# nrf24l01_mboard.net
KiCad netlist of a schematic drawn in Altium Designer
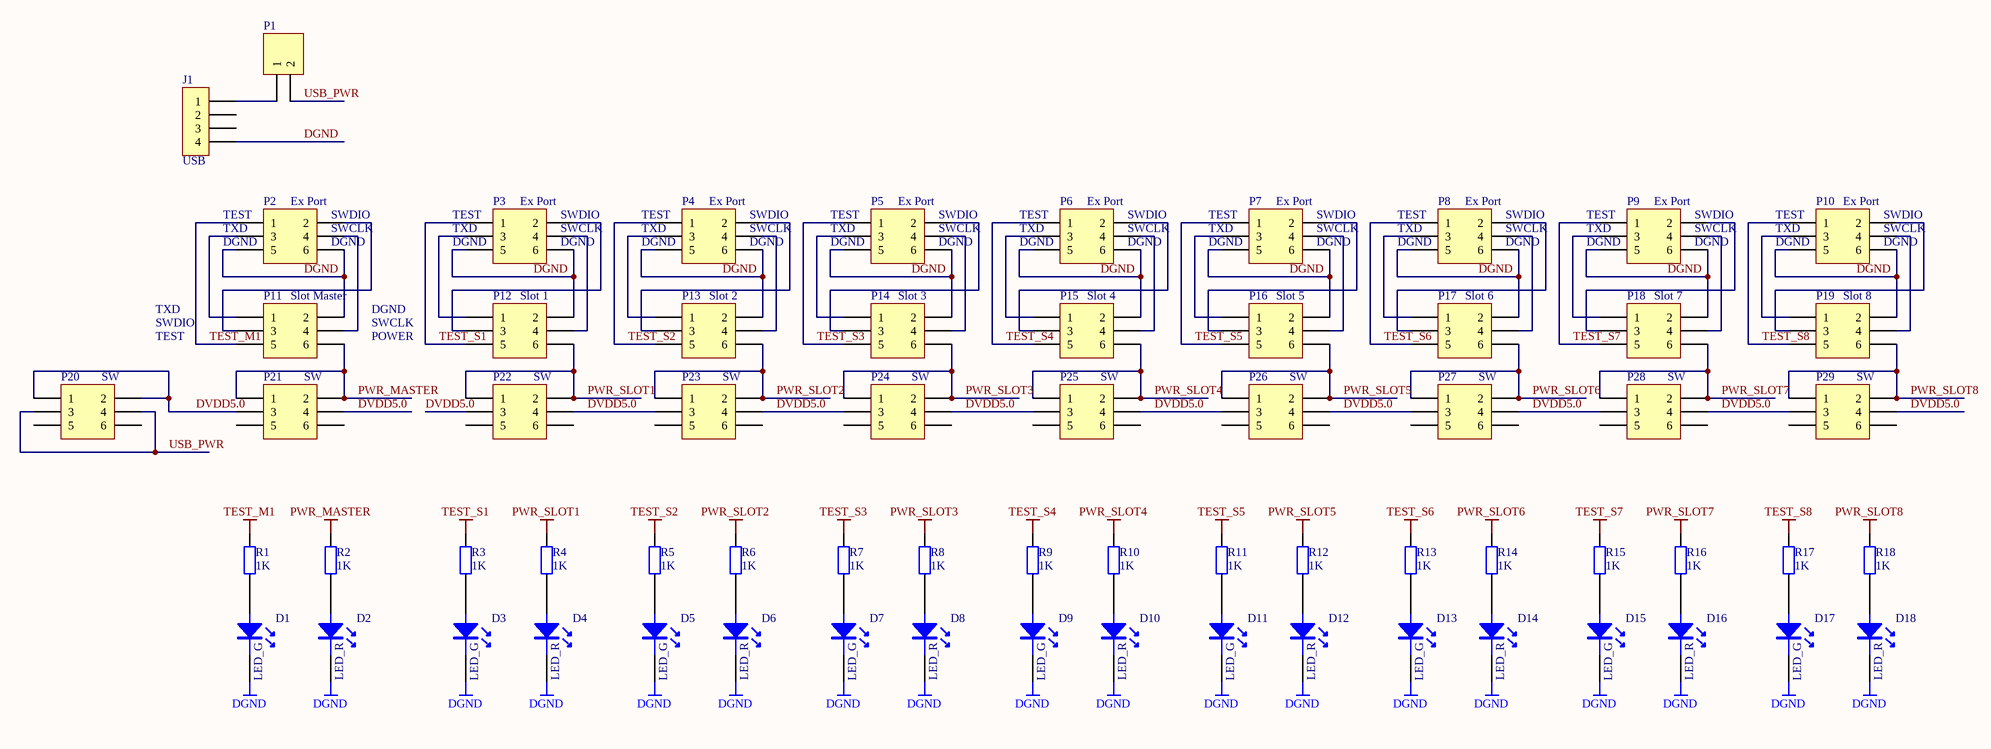
[diagram p0: nrf24l01_mboard.SchDoc]

(export (version "E")
  (design (tool "Eeschema 10.0.6"))
  (components
    (comp (ref "D1") (value "LED_G") (footprint "LED-0603R") (libsource (lib "*") (part "LED")))
    (comp (ref "D2") (value "LED_R") (footprint "LED-0603R") (libsource (lib "*") (part "LED")))
    (comp (ref "D3") (value "LED_G") (footprint "LED-0603R") (libsource (lib "*") (part "LED")))
    (comp (ref "D4") (value "LED_R") (footprint "LED-0603R") (libsource (lib "*") (part "LED")))
    (comp (ref "D5") (value "LED_G") (footprint "LED-0603R") (libsource (lib "*") (part "LED")))
    (comp (ref "D6") (value "LED_R") (footprint "LED-0603R") (libsource (lib "*") (part "LED")))
    (comp (ref "D7") (value "LED_G") (footprint "LED-0603R") (libsource (lib "*") (part "LED")))
    (comp (ref "D8") (value "LED_R") (footprint "LED-0603R") (libsource (lib "*") (part "LED")))
    (comp (ref "D9") (value "LED_G") (footprint "LED-0603R") (libsource (lib "*") (part "LED")))
    (comp (ref "D10") (value "LED_R") (footprint "LED-0603R") (libsource (lib "*") (part "LED")))
    (comp (ref "D11") (value "LED_G") (footprint "LED-0603R") (libsource (lib "*") (part "LED")))
    (comp (ref "D12") (value "LED_R") (footprint "LED-0603R") (libsource (lib "*") (part "LED")))
    (comp (ref "D13") (value "LED_G") (footprint "LED-0603R") (libsource (lib "*") (part "LED")))
    (comp (ref "D14") (value "LED_R") (footprint "LED-0603R") (libsource (lib "*") (part "LED")))
    (comp (ref "D15") (value "LED_G") (footprint "LED-0603R") (libsource (lib "*") (part "LED")))
    (comp (ref "D16") (value "LED_R") (footprint "LED-0603R") (libsource (lib "*") (part "LED")))
    (comp (ref "D17") (value "LED_G") (footprint "LED-0603R") (libsource (lib "*") (part "LED")))
    (comp (ref "D18") (value "LED_R") (footprint "LED-0603R") (libsource (lib "*") (part "LED")))
    (comp (ref "J1")
      (value "USB")
      (footprint "USB-MINIB")
      (description "Connector")
      (libsource (lib "*") (part "CON4"))
    )
    (comp (ref "P1")
      (value "~")
      (footprint "HDR1X2")
      (description "Header, 2-Pin")
      (fields (field (name "PUBLISHER") "Altium Limited"))
      (libsource (lib "Miscellaneous Connectors") (part "Header 2"))
    )
    (comp (ref "P2")
      (value "Ex Port")
      (footprint "IDC6")
      (description "Header, 3-Pin, Dual row")
      (fields (field (name "PUBLISHER") "Altium Limited"))
      (libsource (lib "Miscellaneous Connectors") (part "Header 3X2"))
    )
    (comp (ref "P3")
      (value "Ex Port")
      (footprint "IDC6")
      (description "Header, 3-Pin, Dual row")
      (fields (field (name "PUBLISHER") "Altium Limited"))
      (libsource (lib "Miscellaneous Connectors") (part "Header 3X2"))
    )
    (comp (ref "P4")
      (value "Ex Port")
      (footprint "IDC6")
      (description "Header, 3-Pin, Dual row")
      (fields (field (name "PUBLISHER") "Altium Limited"))
      (libsource (lib "Miscellaneous Connectors") (part "Header 3X2"))
    )
    (comp (ref "P5")
      (value "Ex Port")
      (footprint "IDC6")
      (description "Header, 3-Pin, Dual row")
      (fields (field (name "PUBLISHER") "Altium Limited"))
      (libsource (lib "Miscellaneous Connectors") (part "Header 3X2"))
    )
    (comp (ref "P6")
      (value "Ex Port")
      (footprint "IDC6")
      (description "Header, 3-Pin, Dual row")
      (fields (field (name "PUBLISHER") "Altium Limited"))
      (libsource (lib "Miscellaneous Connectors") (part "Header 3X2"))
    )
    (comp (ref "P7")
      (value "Ex Port")
      (footprint "IDC6")
      (description "Header, 3-Pin, Dual row")
      (fields (field (name "PUBLISHER") "Altium Limited"))
      (libsource (lib "Miscellaneous Connectors") (part "Header 3X2"))
    )
    (comp (ref "P8")
      (value "Ex Port")
      (footprint "IDC6")
      (description "Header, 3-Pin, Dual row")
      (fields (field (name "PUBLISHER") "Altium Limited"))
      (libsource (lib "Miscellaneous Connectors") (part "Header 3X2"))
    )
    (comp (ref "P9")
      (value "Ex Port")
      (footprint "IDC6")
      (description "Header, 3-Pin, Dual row")
      (fields (field (name "PUBLISHER") "Altium Limited"))
      (libsource (lib "Miscellaneous Connectors") (part "Header 3X2"))
    )
    (comp (ref "P10")
      (value "Ex Port")
      (footprint "IDC6")
      (description "Header, 3-Pin, Dual row")
      (fields (field (name "PUBLISHER") "Altium Limited"))
      (libsource (lib "Miscellaneous Connectors") (part "Header 3X2"))
    )
    (comp (ref "P11")
      (value "Slot Master")
      (footprint "S-8M-2.54-5 6P")
      (description "Header, 3-Pin, Dual row")
      (fields (field (name "PUBLISHER") "Altium Limited"))
      (libsource (lib "Miscellaneous Connectors") (part "Header 3X2"))
    )
    (comp (ref "P12")
      (value "Slot 1")
      (footprint "S-8M-2.54-5 6P")
      (description "Header, 3-Pin, Dual row")
      (fields (field (name "PUBLISHER") "Altium Limited"))
      (libsource (lib "Miscellaneous Connectors") (part "Header 3X2"))
    )
    (comp (ref "P13")
      (value "Slot 2")
      (footprint "S-8M-2.54-5 6P")
      (description "Header, 3-Pin, Dual row")
      (fields (field (name "PUBLISHER") "Altium Limited"))
      (libsource (lib "Miscellaneous Connectors") (part "Header 3X2"))
    )
    (comp (ref "P14")
      (value "Slot 3")
      (footprint "S-8M-2.54-5 6P")
      (description "Header, 3-Pin, Dual row")
      (fields (field (name "PUBLISHER") "Altium Limited"))
      (libsource (lib "Miscellaneous Connectors") (part "Header 3X2"))
    )
    (comp (ref "P15")
      (value "Slot 4")
      (footprint "S-8M-2.54-5 6P")
      (description "Header, 3-Pin, Dual row")
      (fields (field (name "PUBLISHER") "Altium Limited"))
      (libsource (lib "Miscellaneous Connectors") (part "Header 3X2"))
    )
    (comp (ref "P16")
      (value "Slot 5")
      (footprint "S-8M-2.54-5 6P")
      (description "Header, 3-Pin, Dual row")
      (fields (field (name "PUBLISHER") "Altium Limited"))
      (libsource (lib "Miscellaneous Connectors") (part "Header 3X2"))
    )
    (comp (ref "P17")
      (value "Slot 6")
      (footprint "S-8M-2.54-5 6P")
      (description "Header, 3-Pin, Dual row")
      (fields (field (name "PUBLISHER") "Altium Limited"))
      (libsource (lib "Miscellaneous Connectors") (part "Header 3X2"))
    )
    (comp (ref "P18")
      (value "Slot 7")
      (footprint "S-8M-2.54-5 6P")
      (description "Header, 3-Pin, Dual row")
      (fields (field (name "PUBLISHER") "Altium Limited"))
      (libsource (lib "Miscellaneous Connectors") (part "Header 3X2"))
    )
    (comp (ref "P19")
      (value "Slot 8")
      (footprint "S-8M-2.54-5 6P")
      (description "Header, 3-Pin, Dual row")
      (fields (field (name "PUBLISHER") "Altium Limited"))
      (libsource (lib "Miscellaneous Connectors") (part "Header 3X2"))
    )
    (comp (ref "P20")
      (value "SW")
      (footprint "SW-7x7")
      (description "Header, 3-Pin, Dual row")
      (fields (field (name "PUBLISHER") "Altium Limited"))
      (libsource (lib "Miscellaneous Connectors") (part "Header 3X2"))
    )
    (comp (ref "P21")
      (value "SW")
      (footprint "SW-7x7")
      (description "Header, 3-Pin, Dual row")
      (fields (field (name "PUBLISHER") "Altium Limited"))
      (libsource (lib "Miscellaneous Connectors") (part "Header 3X2"))
    )
    (comp (ref "P22")
      (value "SW")
      (footprint "SW-7x7")
      (description "Header, 3-Pin, Dual row")
      (fields (field (name "PUBLISHER") "Altium Limited"))
      (libsource (lib "Miscellaneous Connectors") (part "Header 3X2"))
    )
    (comp (ref "P23")
      (value "SW")
      (footprint "SW-7x7")
      (description "Header, 3-Pin, Dual row")
      (fields (field (name "PUBLISHER") "Altium Limited"))
      (libsource (lib "Miscellaneous Connectors") (part "Header 3X2"))
    )
    (comp (ref "P24")
      (value "SW")
      (footprint "SW-7x7")
      (description "Header, 3-Pin, Dual row")
      (fields (field (name "PUBLISHER") "Altium Limited"))
      (libsource (lib "Miscellaneous Connectors") (part "Header 3X2"))
    )
    (comp (ref "P25")
      (value "SW")
      (footprint "SW-7x7")
      (description "Header, 3-Pin, Dual row")
      (fields (field (name "PUBLISHER") "Altium Limited"))
      (libsource (lib "Miscellaneous Connectors") (part "Header 3X2"))
    )
    (comp (ref "P26")
      (value "SW")
      (footprint "SW-7x7")
      (description "Header, 3-Pin, Dual row")
      (fields (field (name "PUBLISHER") "Altium Limited"))
      (libsource (lib "Miscellaneous Connectors") (part "Header 3X2"))
    )
    (comp (ref "P27")
      (value "SW")
      (footprint "SW-7x7")
      (description "Header, 3-Pin, Dual row")
      (fields (field (name "PUBLISHER") "Altium Limited"))
      (libsource (lib "Miscellaneous Connectors") (part "Header 3X2"))
    )
    (comp (ref "P28")
      (value "SW")
      (footprint "SW-7x7")
      (description "Header, 3-Pin, Dual row")
      (fields (field (name "PUBLISHER") "Altium Limited"))
      (libsource (lib "Miscellaneous Connectors") (part "Header 3X2"))
    )
    (comp (ref "P29")
      (value "SW")
      (footprint "SW-7x7")
      (description "Header, 3-Pin, Dual row")
      (fields (field (name "PUBLISHER") "Altium Limited"))
      (libsource (lib "Miscellaneous Connectors") (part "Header 3X2"))
    )
    (comp (ref "R1")
      (value "1K")
      (footprint "1608(0603R)")
      (description "Resistor")
      (fields (field (name "PUBLISHER") "Altium Limited"))
      (libsource (lib "Miscellaneous Devices") (part "Res2"))
    )
    (comp (ref "R2")
      (value "1K")
      (footprint "1608(0603R)")
      (description "Resistor")
      (fields (field (name "PUBLISHER") "Altium Limited"))
      (libsource (lib "Miscellaneous Devices") (part "Res2"))
    )
    (comp (ref "R3")
      (value "1K")
      (footprint "1608(0603R)")
      (description "Resistor")
      (fields (field (name "PUBLISHER") "Altium Limited"))
      (libsource (lib "Miscellaneous Devices") (part "Res2"))
    )
    (comp (ref "R4")
      (value "1K")
      (footprint "1608(0603R)")
      (description "Resistor")
      (fields (field (name "PUBLISHER") "Altium Limited"))
      (libsource (lib "Miscellaneous Devices") (part "Res2"))
    )
    (comp (ref "R5")
      (value "1K")
      (footprint "1608(0603R)")
      (description "Resistor")
      (fields (field (name "PUBLISHER") "Altium Limited"))
      (libsource (lib "Miscellaneous Devices") (part "Res2"))
    )
    (comp (ref "R6")
      (value "1K")
      (footprint "1608(0603R)")
      (description "Resistor")
      (fields (field (name "PUBLISHER") "Altium Limited"))
      (libsource (lib "Miscellaneous Devices") (part "Res2"))
    )
    (comp (ref "R7")
      (value "1K")
      (footprint "1608(0603R)")
      (description "Resistor")
      (fields (field (name "PUBLISHER") "Altium Limited"))
      (libsource (lib "Miscellaneous Devices") (part "Res2"))
    )
    (comp (ref "R8")
      (value "1K")
      (footprint "1608(0603R)")
      (description "Resistor")
      (fields (field (name "PUBLISHER") "Altium Limited"))
      (libsource (lib "Miscellaneous Devices") (part "Res2"))
    )
    (comp (ref "R9")
      (value "1K")
      (footprint "1608(0603R)")
      (description "Resistor")
      (fields (field (name "PUBLISHER") "Altium Limited"))
      (libsource (lib "Miscellaneous Devices") (part "Res2"))
    )
    (comp (ref "R10")
      (value "1K")
      (footprint "1608(0603R)")
      (description "Resistor")
      (fields (field (name "PUBLISHER") "Altium Limited"))
      (libsource (lib "Miscellaneous Devices") (part "Res2"))
    )
    (comp (ref "R11")
      (value "1K")
      (footprint "1608(0603R)")
      (description "Resistor")
      (fields (field (name "PUBLISHER") "Altium Limited"))
      (libsource (lib "Miscellaneous Devices") (part "Res2"))
    )
    (comp (ref "R12")
      (value "1K")
      (footprint "1608(0603R)")
      (description "Resistor")
      (fields (field (name "PUBLISHER") "Altium Limited"))
      (libsource (lib "Miscellaneous Devices") (part "Res2"))
    )
    (comp (ref "R13")
      (value "1K")
      (footprint "1608(0603R)")
      (description "Resistor")
      (fields (field (name "PUBLISHER") "Altium Limited"))
      (libsource (lib "Miscellaneous Devices") (part "Res2"))
    )
    (comp (ref "R14")
      (value "1K")
      (footprint "1608(0603R)")
      (description "Resistor")
      (fields (field (name "PUBLISHER") "Altium Limited"))
      (libsource (lib "Miscellaneous Devices") (part "Res2"))
    )
    (comp (ref "R15")
      (value "1K")
      (footprint "1608(0603R)")
      (description "Resistor")
      (fields (field (name "PUBLISHER") "Altium Limited"))
      (libsource (lib "Miscellaneous Devices") (part "Res2"))
    )
    (comp (ref "R16")
      (value "1K")
      (footprint "1608(0603R)")
      (description "Resistor")
      (fields (field (name "PUBLISHER") "Altium Limited"))
      (libsource (lib "Miscellaneous Devices") (part "Res2"))
    )
    (comp (ref "R17")
      (value "1K")
      (footprint "1608(0603R)")
      (description "Resistor")
      (fields (field (name "PUBLISHER") "Altium Limited"))
      (libsource (lib "Miscellaneous Devices") (part "Res2"))
    )
    (comp (ref "R18")
      (value "1K")
      (footprint "1608(0603R)")
      (description "Resistor")
      (fields (field (name "PUBLISHER") "Altium Limited"))
      (libsource (lib "Miscellaneous Devices") (part "Res2"))
    )
  )
  (nets
    (net (code "1") (name "/DVDD5.0") (class "Default")
      (node (ref "P20") (pin "1") (pinfunction "1_1") (pintype "passive"))
      (node (ref "P20") (pin "2") (pinfunction "2_2") (pintype "passive"))
      (node (ref "P21") (pin "3") (pinfunction "3_3") (pintype "passive"))
      (node (ref "P21") (pin "4") (pinfunction "4_4") (pintype "passive"))
      (node (ref "P22") (pin "3") (pinfunction "3_3") (pintype "passive"))
      (node (ref "P22") (pin "4") (pinfunction "4_4") (pintype "passive"))
      (node (ref "P23") (pin "3") (pinfunction "3_3") (pintype "passive"))
      (node (ref "P23") (pin "4") (pinfunction "4_4") (pintype "passive"))
      (node (ref "P24") (pin "3") (pinfunction "3_3") (pintype "passive"))
      (node (ref "P24") (pin "4") (pinfunction "4_4") (pintype "passive"))
      (node (ref "P25") (pin "3") (pinfunction "3_3") (pintype "passive"))
      (node (ref "P25") (pin "4") (pinfunction "4_4") (pintype "passive"))
      (node (ref "P26") (pin "3") (pinfunction "3_3") (pintype "passive"))
      (node (ref "P26") (pin "4") (pinfunction "4_4") (pintype "passive"))
      (node (ref "P27") (pin "3") (pinfunction "3_3") (pintype "passive"))
      (node (ref "P27") (pin "4") (pinfunction "4_4") (pintype "passive"))
      (node (ref "P28") (pin "3") (pinfunction "3_3") (pintype "passive"))
      (node (ref "P28") (pin "4") (pinfunction "4_4") (pintype "passive"))
      (node (ref "P29") (pin "3") (pinfunction "3_3") (pintype "passive"))
      (node (ref "P29") (pin "4") (pinfunction "4_4") (pintype "passive"))
    )
    (net (code "2") (name "/USB_PWR") (class "Default")
      (node (ref "P1") (pin "2") (pinfunction "2_2") (pintype "passive"))
      (node (ref "P20") (pin "3") (pinfunction "3_3") (pintype "passive"))
      (node (ref "P20") (pin "4") (pinfunction "4_4") (pintype "passive"))
    )
    (net (code "3") (name "DGND") (class "Default")
      (node (ref "D1") (pin "K") (pinfunction "2_K") (pintype "passive"))
      (node (ref "D10") (pin "K") (pinfunction "2_K") (pintype "passive"))
      (node (ref "D11") (pin "K") (pinfunction "2_K") (pintype "passive"))
      (node (ref "D12") (pin "K") (pinfunction "2_K") (pintype "passive"))
      (node (ref "D13") (pin "K") (pinfunction "2_K") (pintype "passive"))
      (node (ref "D14") (pin "K") (pinfunction "2_K") (pintype "passive"))
      (node (ref "D15") (pin "K") (pinfunction "2_K") (pintype "passive"))
      (node (ref "D16") (pin "K") (pinfunction "2_K") (pintype "passive"))
      (node (ref "D17") (pin "K") (pinfunction "2_K") (pintype "passive"))
      (node (ref "D18") (pin "K") (pinfunction "2_K") (pintype "passive"))
      (node (ref "D2") (pin "K") (pinfunction "2_K") (pintype "passive"))
      (node (ref "D3") (pin "K") (pinfunction "2_K") (pintype "passive"))
      (node (ref "D4") (pin "K") (pinfunction "2_K") (pintype "passive"))
      (node (ref "D5") (pin "K") (pinfunction "2_K") (pintype "passive"))
      (node (ref "D6") (pin "K") (pinfunction "2_K") (pintype "passive"))
      (node (ref "D7") (pin "K") (pinfunction "2_K") (pintype "passive"))
      (node (ref "D8") (pin "K") (pinfunction "2_K") (pintype "passive"))
      (node (ref "D9") (pin "K") (pinfunction "2_K") (pintype "passive"))
      (node (ref "J1") (pin "4") (pinfunction "4_4") (pintype "passive"))
      (node (ref "P10") (pin "5") (pinfunction "5_5") (pintype "passive"))
      (node (ref "P10") (pin "6") (pinfunction "6_6") (pintype "passive"))
      (node (ref "P11") (pin "2") (pinfunction "2_2") (pintype "passive"))
      (node (ref "P12") (pin "2") (pinfunction "2_2") (pintype "passive"))
      (node (ref "P13") (pin "2") (pinfunction "2_2") (pintype "passive"))
      (node (ref "P14") (pin "2") (pinfunction "2_2") (pintype "passive"))
      (node (ref "P15") (pin "2") (pinfunction "2_2") (pintype "passive"))
      (node (ref "P16") (pin "2") (pinfunction "2_2") (pintype "passive"))
      (node (ref "P17") (pin "2") (pinfunction "2_2") (pintype "passive"))
      (node (ref "P18") (pin "2") (pinfunction "2_2") (pintype "passive"))
      (node (ref "P19") (pin "2") (pinfunction "2_2") (pintype "passive"))
      (node (ref "P2") (pin "5") (pinfunction "5_5") (pintype "passive"))
      (node (ref "P2") (pin "6") (pinfunction "6_6") (pintype "passive"))
      (node (ref "P3") (pin "5") (pinfunction "5_5") (pintype "passive"))
      (node (ref "P3") (pin "6") (pinfunction "6_6") (pintype "passive"))
      (node (ref "P4") (pin "5") (pinfunction "5_5") (pintype "passive"))
      (node (ref "P4") (pin "6") (pinfunction "6_6") (pintype "passive"))
      (node (ref "P5") (pin "5") (pinfunction "5_5") (pintype "passive"))
      (node (ref "P5") (pin "6") (pinfunction "6_6") (pintype "passive"))
      (node (ref "P6") (pin "5") (pinfunction "5_5") (pintype "passive"))
      (node (ref "P6") (pin "6") (pinfunction "6_6") (pintype "passive"))
      (node (ref "P7") (pin "5") (pinfunction "5_5") (pintype "passive"))
      (node (ref "P7") (pin "6") (pinfunction "6_6") (pintype "passive"))
      (node (ref "P8") (pin "5") (pinfunction "5_5") (pintype "passive"))
      (node (ref "P8") (pin "6") (pinfunction "6_6") (pintype "passive"))
      (node (ref "P9") (pin "5") (pinfunction "5_5") (pintype "passive"))
      (node (ref "P9") (pin "6") (pinfunction "6_6") (pintype "passive"))
    )
    (net (code "4") (name "Net-(D1-1)") (class "Default")
      (node (ref "D1") (pin "A") (pinfunction "1_A") (pintype "passive"))
      (node (ref "R1") (pin "2") (pinfunction "2_2") (pintype "passive"))
    )
    (net (code "5") (name "Net-(D2-1)") (class "Default")
      (node (ref "D2") (pin "A") (pinfunction "1_A") (pintype "passive"))
      (node (ref "R2") (pin "2") (pinfunction "2_2") (pintype "passive"))
    )
    (net (code "6") (name "Net-(D3-1)") (class "Default")
      (node (ref "D3") (pin "A") (pinfunction "1_A") (pintype "passive"))
      (node (ref "R3") (pin "2") (pinfunction "2_2") (pintype "passive"))
    )
    (net (code "7") (name "Net-(D4-1)") (class "Default")
      (node (ref "D4") (pin "A") (pinfunction "1_A") (pintype "passive"))
      (node (ref "R4") (pin "2") (pinfunction "2_2") (pintype "passive"))
    )
    (net (code "8") (name "Net-(D5-1)") (class "Default")
      (node (ref "D5") (pin "A") (pinfunction "1_A") (pintype "passive"))
      (node (ref "R5") (pin "2") (pinfunction "2_2") (pintype "passive"))
    )
    (net (code "9") (name "Net-(D6-1)") (class "Default")
      (node (ref "D6") (pin "A") (pinfunction "1_A") (pintype "passive"))
      (node (ref "R6") (pin "2") (pinfunction "2_2") (pintype "passive"))
    )
    (net (code "10") (name "Net-(D7-1)") (class "Default")
      (node (ref "D7") (pin "A") (pinfunction "1_A") (pintype "passive"))
      (node (ref "R7") (pin "2") (pinfunction "2_2") (pintype "passive"))
    )
    (net (code "11") (name "Net-(D8-1)") (class "Default")
      (node (ref "D8") (pin "A") (pinfunction "1_A") (pintype "passive"))
      (node (ref "R8") (pin "2") (pinfunction "2_2") (pintype "passive"))
    )
    (net (code "12") (name "Net-(D9-1)") (class "Default")
      (node (ref "D9") (pin "A") (pinfunction "1_A") (pintype "passive"))
      (node (ref "R9") (pin "2") (pinfunction "2_2") (pintype "passive"))
    )
    (net (code "13") (name "Net-(D10-1)") (class "Default")
      (node (ref "D10") (pin "A") (pinfunction "1_A") (pintype "passive"))
      (node (ref "R10") (pin "2") (pinfunction "2_2") (pintype "passive"))
    )
    (net (code "14") (name "Net-(D11-1)") (class "Default")
      (node (ref "D11") (pin "A") (pinfunction "1_A") (pintype "passive"))
      (node (ref "R11") (pin "2") (pinfunction "2_2") (pintype "passive"))
    )
    (net (code "15") (name "Net-(D12-1)") (class "Default")
      (node (ref "D12") (pin "A") (pinfunction "1_A") (pintype "passive"))
      (node (ref "R12") (pin "2") (pinfunction "2_2") (pintype "passive"))
    )
    (net (code "16") (name "Net-(D13-1)") (class "Default")
      (node (ref "D13") (pin "A") (pinfunction "1_A") (pintype "passive"))
      (node (ref "R13") (pin "2") (pinfunction "2_2") (pintype "passive"))
    )
    (net (code "17") (name "Net-(D14-1)") (class "Default")
      (node (ref "D14") (pin "A") (pinfunction "1_A") (pintype "passive"))
      (node (ref "R14") (pin "2") (pinfunction "2_2") (pintype "passive"))
    )
    (net (code "18") (name "Net-(D15-1)") (class "Default")
      (node (ref "D15") (pin "A") (pinfunction "1_A") (pintype "passive"))
      (node (ref "R15") (pin "2") (pinfunction "2_2") (pintype "passive"))
    )
    (net (code "19") (name "Net-(D16-1)") (class "Default")
      (node (ref "D16") (pin "A") (pinfunction "1_A") (pintype "passive"))
      (node (ref "R16") (pin "2") (pinfunction "2_2") (pintype "passive"))
    )
    (net (code "20") (name "Net-(D17-1)") (class "Default")
      (node (ref "D17") (pin "A") (pinfunction "1_A") (pintype "passive"))
      (node (ref "R17") (pin "2") (pinfunction "2_2") (pintype "passive"))
    )
    (net (code "21") (name "Net-(D18-1)") (class "Default")
      (node (ref "D18") (pin "A") (pinfunction "1_A") (pintype "passive"))
      (node (ref "R18") (pin "2") (pinfunction "2_2") (pintype "passive"))
    )
    (net (code "22") (name "Net-(J1-Pad1)") (class "Default")
      (node (ref "J1") (pin "1") (pinfunction "1_1") (pintype "passive"))
      (node (ref "P1") (pin "1") (pinfunction "1_1") (pintype "passive"))
    )
    (net (code "23") (name "Net-(P10-Pad2)") (class "Default")
      (node (ref "P10") (pin "2") (pinfunction "2_2") (pintype "passive"))
      (node (ref "P19") (pin "3") (pinfunction "3_3") (pintype "passive"))
    )
    (net (code "24") (name "Net-(P10-Pad3)") (class "Default")
      (node (ref "P10") (pin "3") (pinfunction "3_3") (pintype "passive"))
      (node (ref "P19") (pin "1") (pinfunction "1_1") (pintype "passive"))
    )
    (net (code "25") (name "Net-(P10-Pad4)") (class "Default")
      (node (ref "P10") (pin "4") (pinfunction "4_4") (pintype "passive"))
      (node (ref "P19") (pin "4") (pinfunction "4_4") (pintype "passive"))
    )
    (net (code "26") (name "Net-(P11-Pad1)") (class "Default")
      (node (ref "P11") (pin "1") (pinfunction "1_1") (pintype "passive"))
      (node (ref "P2") (pin "3") (pinfunction "3_3") (pintype "passive"))
    )
    (net (code "27") (name "Net-(P11-Pad3)") (class "Default")
      (node (ref "P11") (pin "3") (pinfunction "3_3") (pintype "passive"))
      (node (ref "P2") (pin "2") (pinfunction "2_2") (pintype "passive"))
    )
    (net (code "28") (name "Net-(P11-Pad4)") (class "Default")
      (node (ref "P11") (pin "4") (pinfunction "4_4") (pintype "passive"))
      (node (ref "P2") (pin "4") (pinfunction "4_4") (pintype "passive"))
    )
    (net (code "29") (name "Net-(P12-Pad1)") (class "Default")
      (node (ref "P12") (pin "1") (pinfunction "1_1") (pintype "passive"))
      (node (ref "P3") (pin "3") (pinfunction "3_3") (pintype "passive"))
    )
    (net (code "30") (name "Net-(P12-Pad3)") (class "Default")
      (node (ref "P12") (pin "3") (pinfunction "3_3") (pintype "passive"))
      (node (ref "P3") (pin "2") (pinfunction "2_2") (pintype "passive"))
    )
    (net (code "31") (name "Net-(P12-Pad4)") (class "Default")
      (node (ref "P12") (pin "4") (pinfunction "4_4") (pintype "passive"))
      (node (ref "P3") (pin "4") (pinfunction "4_4") (pintype "passive"))
    )
    (net (code "32") (name "Net-(P13-Pad1)") (class "Default")
      (node (ref "P13") (pin "1") (pinfunction "1_1") (pintype "passive"))
      (node (ref "P4") (pin "3") (pinfunction "3_3") (pintype "passive"))
    )
    (net (code "33") (name "Net-(P13-Pad3)") (class "Default")
      (node (ref "P13") (pin "3") (pinfunction "3_3") (pintype "passive"))
      (node (ref "P4") (pin "2") (pinfunction "2_2") (pintype "passive"))
    )
    (net (code "34") (name "Net-(P13-Pad4)") (class "Default")
      (node (ref "P13") (pin "4") (pinfunction "4_4") (pintype "passive"))
      (node (ref "P4") (pin "4") (pinfunction "4_4") (pintype "passive"))
    )
    (net (code "35") (name "Net-(P14-Pad1)") (class "Default")
      (node (ref "P14") (pin "1") (pinfunction "1_1") (pintype "passive"))
      (node (ref "P5") (pin "3") (pinfunction "3_3") (pintype "passive"))
    )
    (net (code "36") (name "Net-(P14-Pad3)") (class "Default")
      (node (ref "P14") (pin "3") (pinfunction "3_3") (pintype "passive"))
      (node (ref "P5") (pin "2") (pinfunction "2_2") (pintype "passive"))
    )
    (net (code "37") (name "Net-(P14-Pad4)") (class "Default")
      (node (ref "P14") (pin "4") (pinfunction "4_4") (pintype "passive"))
      (node (ref "P5") (pin "4") (pinfunction "4_4") (pintype "passive"))
    )
    (net (code "38") (name "Net-(P15-Pad1)") (class "Default")
      (node (ref "P15") (pin "1") (pinfunction "1_1") (pintype "passive"))
      (node (ref "P6") (pin "3") (pinfunction "3_3") (pintype "passive"))
    )
    (net (code "39") (name "Net-(P15-Pad3)") (class "Default")
      (node (ref "P15") (pin "3") (pinfunction "3_3") (pintype "passive"))
      (node (ref "P6") (pin "2") (pinfunction "2_2") (pintype "passive"))
    )
    (net (code "40") (name "Net-(P15-Pad4)") (class "Default")
      (node (ref "P15") (pin "4") (pinfunction "4_4") (pintype "passive"))
      (node (ref "P6") (pin "4") (pinfunction "4_4") (pintype "passive"))
    )
    (net (code "41") (name "Net-(P16-Pad1)") (class "Default")
      (node (ref "P16") (pin "1") (pinfunction "1_1") (pintype "passive"))
      (node (ref "P7") (pin "3") (pinfunction "3_3") (pintype "passive"))
    )
    (net (code "42") (name "Net-(P16-Pad3)") (class "Default")
      (node (ref "P16") (pin "3") (pinfunction "3_3") (pintype "passive"))
      (node (ref "P7") (pin "2") (pinfunction "2_2") (pintype "passive"))
    )
    (net (code "43") (name "Net-(P16-Pad4)") (class "Default")
      (node (ref "P16") (pin "4") (pinfunction "4_4") (pintype "passive"))
      (node (ref "P7") (pin "4") (pinfunction "4_4") (pintype "passive"))
    )
    (net (code "44") (name "Net-(P17-Pad1)") (class "Default")
      (node (ref "P17") (pin "1") (pinfunction "1_1") (pintype "passive"))
      (node (ref "P8") (pin "3") (pinfunction "3_3") (pintype "passive"))
    )
    (net (code "45") (name "Net-(P17-Pad3)") (class "Default")
      (node (ref "P17") (pin "3") (pinfunction "3_3") (pintype "passive"))
      (node (ref "P8") (pin "2") (pinfunction "2_2") (pintype "passive"))
    )
    (net (code "46") (name "Net-(P17-Pad4)") (class "Default")
      (node (ref "P17") (pin "4") (pinfunction "4_4") (pintype "passive"))
      (node (ref "P8") (pin "4") (pinfunction "4_4") (pintype "passive"))
    )
    (net (code "47") (name "Net-(P18-Pad1)") (class "Default")
      (node (ref "P18") (pin "1") (pinfunction "1_1") (pintype "passive"))
      (node (ref "P9") (pin "3") (pinfunction "3_3") (pintype "passive"))
    )
    (net (code "48") (name "Net-(P18-Pad3)") (class "Default")
      (node (ref "P18") (pin "3") (pinfunction "3_3") (pintype "passive"))
      (node (ref "P9") (pin "2") (pinfunction "2_2") (pintype "passive"))
    )
    (net (code "49") (name "Net-(P18-Pad4)") (class "Default")
      (node (ref "P18") (pin "4") (pinfunction "4_4") (pintype "passive"))
      (node (ref "P9") (pin "4") (pinfunction "4_4") (pintype "passive"))
    )
    (net (code "50") (name "PWR_MASTER") (class "Default")
      (node (ref "P11") (pin "6") (pinfunction "6_6") (pintype "passive"))
      (node (ref "P21") (pin "1") (pinfunction "1_1") (pintype "passive"))
      (node (ref "P21") (pin "2") (pinfunction "2_2") (pintype "passive"))
      (node (ref "R2") (pin "1") (pinfunction "1_1") (pintype "passive"))
    )
    (net (code "51") (name "PWR_SLOT1") (class "Default")
      (node (ref "P12") (pin "6") (pinfunction "6_6") (pintype "passive"))
      (node (ref "P22") (pin "1") (pinfunction "1_1") (pintype "passive"))
      (node (ref "P22") (pin "2") (pinfunction "2_2") (pintype "passive"))
      (node (ref "R4") (pin "1") (pinfunction "1_1") (pintype "passive"))
    )
    (net (code "52") (name "PWR_SLOT2") (class "Default")
      (node (ref "P13") (pin "6") (pinfunction "6_6") (pintype "passive"))
      (node (ref "P23") (pin "1") (pinfunction "1_1") (pintype "passive"))
      (node (ref "P23") (pin "2") (pinfunction "2_2") (pintype "passive"))
      (node (ref "R6") (pin "1") (pinfunction "1_1") (pintype "passive"))
    )
    (net (code "53") (name "PWR_SLOT3") (class "Default")
      (node (ref "P14") (pin "6") (pinfunction "6_6") (pintype "passive"))
      (node (ref "P24") (pin "1") (pinfunction "1_1") (pintype "passive"))
      (node (ref "P24") (pin "2") (pinfunction "2_2") (pintype "passive"))
      (node (ref "R8") (pin "1") (pinfunction "1_1") (pintype "passive"))
    )
    (net (code "54") (name "PWR_SLOT4") (class "Default")
      (node (ref "P15") (pin "6") (pinfunction "6_6") (pintype "passive"))
      (node (ref "P25") (pin "1") (pinfunction "1_1") (pintype "passive"))
      (node (ref "P25") (pin "2") (pinfunction "2_2") (pintype "passive"))
      (node (ref "R10") (pin "1") (pinfunction "1_1") (pintype "passive"))
    )
    (net (code "55") (name "PWR_SLOT5") (class "Default")
      (node (ref "P16") (pin "6") (pinfunction "6_6") (pintype "passive"))
      (node (ref "P26") (pin "1") (pinfunction "1_1") (pintype "passive"))
      (node (ref "P26") (pin "2") (pinfunction "2_2") (pintype "passive"))
      (node (ref "R12") (pin "1") (pinfunction "1_1") (pintype "passive"))
    )
    (net (code "56") (name "PWR_SLOT6") (class "Default")
      (node (ref "P17") (pin "6") (pinfunction "6_6") (pintype "passive"))
      (node (ref "P27") (pin "1") (pinfunction "1_1") (pintype "passive"))
      (node (ref "P27") (pin "2") (pinfunction "2_2") (pintype "passive"))
      (node (ref "R14") (pin "1") (pinfunction "1_1") (pintype "passive"))
    )
    (net (code "57") (name "PWR_SLOT7") (class "Default")
      (node (ref "P18") (pin "6") (pinfunction "6_6") (pintype "passive"))
      (node (ref "P28") (pin "1") (pinfunction "1_1") (pintype "passive"))
      (node (ref "P28") (pin "2") (pinfunction "2_2") (pintype "passive"))
      (node (ref "R16") (pin "1") (pinfunction "1_1") (pintype "passive"))
    )
    (net (code "58") (name "PWR_SLOT8") (class "Default")
      (node (ref "P19") (pin "6") (pinfunction "6_6") (pintype "passive"))
      (node (ref "P29") (pin "1") (pinfunction "1_1") (pintype "passive"))
      (node (ref "P29") (pin "2") (pinfunction "2_2") (pintype "passive"))
      (node (ref "R18") (pin "1") (pinfunction "1_1") (pintype "passive"))
    )
    (net (code "59") (name "TEST_M1") (class "Default")
      (node (ref "P11") (pin "5") (pinfunction "5_5") (pintype "passive"))
      (node (ref "P2") (pin "1") (pinfunction "1_1") (pintype "passive"))
      (node (ref "R1") (pin "1") (pinfunction "1_1") (pintype "passive"))
    )
    (net (code "60") (name "TEST_S1") (class "Default")
      (node (ref "P12") (pin "5") (pinfunction "5_5") (pintype "passive"))
      (node (ref "P3") (pin "1") (pinfunction "1_1") (pintype "passive"))
      (node (ref "R3") (pin "1") (pinfunction "1_1") (pintype "passive"))
    )
    (net (code "61") (name "TEST_S2") (class "Default")
      (node (ref "P13") (pin "5") (pinfunction "5_5") (pintype "passive"))
      (node (ref "P4") (pin "1") (pinfunction "1_1") (pintype "passive"))
      (node (ref "R5") (pin "1") (pinfunction "1_1") (pintype "passive"))
    )
    (net (code "62") (name "TEST_S3") (class "Default")
      (node (ref "P14") (pin "5") (pinfunction "5_5") (pintype "passive"))
      (node (ref "P5") (pin "1") (pinfunction "1_1") (pintype "passive"))
      (node (ref "R7") (pin "1") (pinfunction "1_1") (pintype "passive"))
    )
    (net (code "63") (name "TEST_S4") (class "Default")
      (node (ref "P15") (pin "5") (pinfunction "5_5") (pintype "passive"))
      (node (ref "P6") (pin "1") (pinfunction "1_1") (pintype "passive"))
      (node (ref "R9") (pin "1") (pinfunction "1_1") (pintype "passive"))
    )
    (net (code "64") (name "TEST_S5") (class "Default")
      (node (ref "P16") (pin "5") (pinfunction "5_5") (pintype "passive"))
      (node (ref "P7") (pin "1") (pinfunction "1_1") (pintype "passive"))
      (node (ref "R11") (pin "1") (pinfunction "1_1") (pintype "passive"))
    )
    (net (code "65") (name "TEST_S6") (class "Default")
      (node (ref "P17") (pin "5") (pinfunction "5_5") (pintype "passive"))
      (node (ref "P8") (pin "1") (pinfunction "1_1") (pintype "passive"))
      (node (ref "R13") (pin "1") (pinfunction "1_1") (pintype "passive"))
    )
    (net (code "66") (name "TEST_S7") (class "Default")
      (node (ref "P18") (pin "5") (pinfunction "5_5") (pintype "passive"))
      (node (ref "P9") (pin "1") (pinfunction "1_1") (pintype "passive"))
      (node (ref "R15") (pin "1") (pinfunction "1_1") (pintype "passive"))
    )
    (net (code "67") (name "TEST_S8") (class "Default")
      (node (ref "P10") (pin "1") (pinfunction "1_1") (pintype "passive"))
      (node (ref "P19") (pin "5") (pinfunction "5_5") (pintype "passive"))
      (node (ref "R17") (pin "1") (pinfunction "1_1") (pintype "passive"))
    )
    (net (code "68") (name "unconnected-(J1-Pad2)") (class "Default")
      (node (ref "J1") (pin "2") (pinfunction "2_2") (pintype "passive"))
    )
    (net (code "69") (name "unconnected-(J1-Pad3)") (class "Default")
      (node (ref "J1") (pin "3") (pinfunction "3_3") (pintype "passive"))
    )
    (net (code "70") (name "unconnected-(P20-Pad5)") (class "Default")
      (node (ref "P20") (pin "5") (pinfunction "5_5") (pintype "passive"))
    )
    (net (code "71") (name "unconnected-(P20-Pad6)") (class "Default")
      (node (ref "P20") (pin "6") (pinfunction "6_6") (pintype "passive"))
    )
    (net (code "72") (name "unconnected-(P21-Pad5)") (class "Default")
      (node (ref "P21") (pin "5") (pinfunction "5_5") (pintype "passive"))
    )
    (net (code "73") (name "unconnected-(P21-Pad6)") (class "Default")
      (node (ref "P21") (pin "6") (pinfunction "6_6") (pintype "passive"))
    )
    (net (code "74") (name "unconnected-(P22-Pad5)") (class "Default")
      (node (ref "P22") (pin "5") (pinfunction "5_5") (pintype "passive"))
    )
    (net (code "75") (name "unconnected-(P22-Pad6)") (class "Default")
      (node (ref "P22") (pin "6") (pinfunction "6_6") (pintype "passive"))
    )
    (net (code "76") (name "unconnected-(P23-Pad5)") (class "Default")
      (node (ref "P23") (pin "5") (pinfunction "5_5") (pintype "passive"))
    )
    (net (code "77") (name "unconnected-(P23-Pad6)") (class "Default")
      (node (ref "P23") (pin "6") (pinfunction "6_6") (pintype "passive"))
    )
    (net (code "78") (name "unconnected-(P24-Pad5)") (class "Default")
      (node (ref "P24") (pin "5") (pinfunction "5_5") (pintype "passive"))
    )
    (net (code "79") (name "unconnected-(P24-Pad6)") (class "Default")
      (node (ref "P24") (pin "6") (pinfunction "6_6") (pintype "passive"))
    )
    (net (code "80") (name "unconnected-(P25-Pad5)") (class "Default")
      (node (ref "P25") (pin "5") (pinfunction "5_5") (pintype "passive"))
    )
    (net (code "81") (name "unconnected-(P25-Pad6)") (class "Default")
      (node (ref "P25") (pin "6") (pinfunction "6_6") (pintype "passive"))
    )
    (net (code "82") (name "unconnected-(P26-Pad5)") (class "Default")
      (node (ref "P26") (pin "5") (pinfunction "5_5") (pintype "passive"))
    )
    (net (code "83") (name "unconnected-(P26-Pad6)") (class "Default")
      (node (ref "P26") (pin "6") (pinfunction "6_6") (pintype "passive"))
    )
    (net (code "84") (name "unconnected-(P27-Pad5)") (class "Default")
      (node (ref "P27") (pin "5") (pinfunction "5_5") (pintype "passive"))
    )
    (net (code "85") (name "unconnected-(P27-Pad6)") (class "Default")
      (node (ref "P27") (pin "6") (pinfunction "6_6") (pintype "passive"))
    )
    (net (code "86") (name "unconnected-(P28-Pad5)") (class "Default")
      (node (ref "P28") (pin "5") (pinfunction "5_5") (pintype "passive"))
    )
    (net (code "87") (name "unconnected-(P28-Pad6)") (class "Default")
      (node (ref "P28") (pin "6") (pinfunction "6_6") (pintype "passive"))
    )
    (net (code "88") (name "unconnected-(P29-Pad5)") (class "Default")
      (node (ref "P29") (pin "5") (pinfunction "5_5") (pintype "passive"))
    )
    (net (code "89") (name "unconnected-(P29-Pad6)") (class "Default")
      (node (ref "P29") (pin "6") (pinfunction "6_6") (pintype "passive"))
    )
  )
)
